# Port.net
KiCad netlist of a schematic drawn in Altium Designer
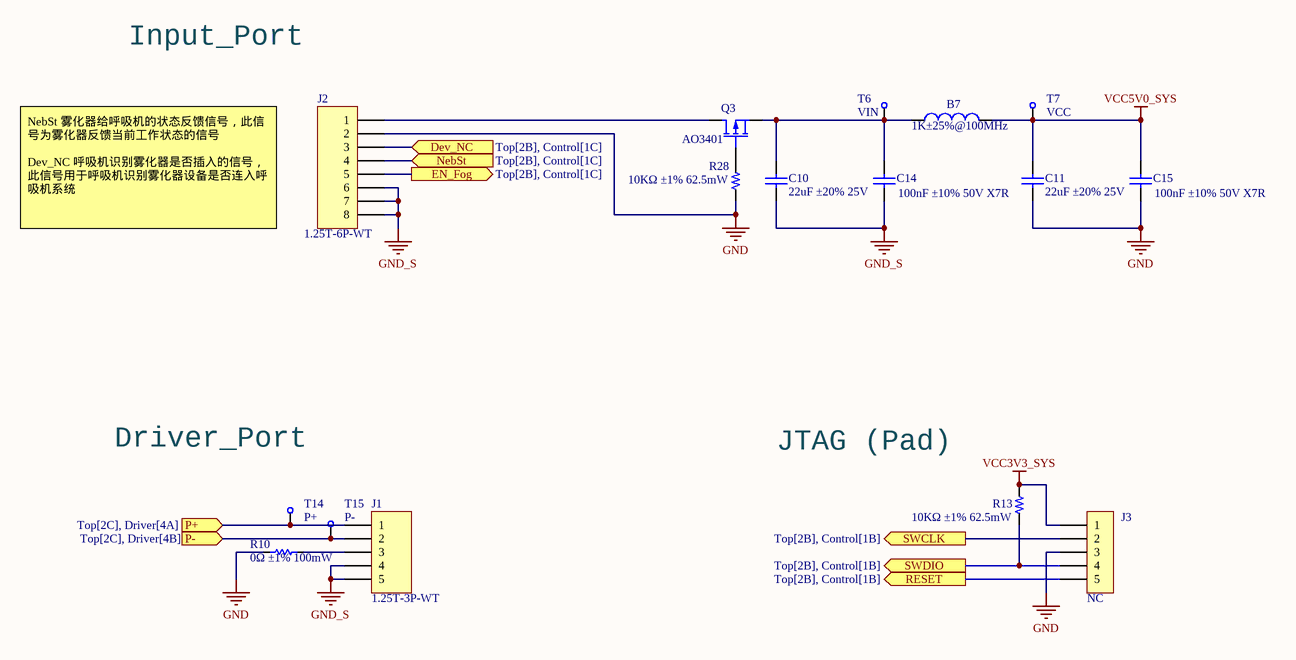
[diagram p0: Port.SchDoc]

(export (version "E")
  (design (tool "Eeschema 10.0.6"))
  (components
    (comp (ref "B7")
      (value "1K±25%@100MHz")
      (footprint "0805-B")
      (description "BLM21AG102SN1D")
      (fields (field (name "PUBLISHER") "Altium Limited"))
      (libsource (lib "Miscellaneous Devices") (part "Inductor"))
    )
    (comp (ref "C10")
      (value "22uF ±20% 25V")
      (footprint "C0805")
      (description "CL21A226MAQNNNE")
      (fields (field (name "PUBLISHER") "Altium Limited"))
      (libsource (lib "Component") (part "C0805"))
    )
    (comp (ref "C11")
      (value "22uF ±20% 25V")
      (footprint "C0805")
      (description "CL21A226MAQNNNE")
      (fields (field (name "PUBLISHER") "Altium Limited"))
      (libsource (lib "Component") (part "C0805"))
    )
    (comp (ref "C14")
      (value "100nF ±10% 50V X7R")
      (footprint "C0402")
      (description "CL05B104KO5NNNC")
      (fields (field (name "PUBLISHER") "Altium Limited"))
      (libsource (lib "Component") (part "Cap"))
    )
    (comp (ref "C15")
      (value "100nF ±10% 50V X7R")
      (footprint "C0402")
      (description "CL05B104KO5NNNC")
      (fields (field (name "PUBLISHER") "Altium Limited"))
      (libsource (lib "Component") (part "Cap"))
    )
    (comp (ref "J1")
      (value "1.25T-3P-WT")
      (footprint "WAFER_1.25MMX3P_180")
      (fields (field (name "PUBLISHER") "Altium Limited"))
      (libsource (lib "Miscellaneous Connectors") (part "Header 5"))
    )
    (comp (ref "J2")
      (value "1.25T-6P-WT")
      (footprint "WAFER_1.25MMX6P_180")
      (fields (field (name "PUBLISHER") "Altium Limited"))
      (libsource (lib "Miscellaneous Connectors") (part "Header 8"))
    )
    (comp (ref "J3")
      (value "NC")
      (footprint "JST_PH 2.00-5")
      (description "品牌：JST 型号：B5B-PH-K-S，直插，间距2.00，5pin")
      (libsource (lib "connectors") (part "JST_PH 2.00-5"))
    )
    (comp (ref "Q3")
      (value "AO3401")
      (footprint "SOT23")
      (fields (field (name "PUBLISHER") "Altium Limited"))
      (libsource (lib "Nebulizer_medical") (part "MOSFET-P"))
    )
    (comp (ref "R10")
      (value "0Ω ±1% 100mW")
      (footprint "R0603")
      (description "0603WAF0000T5E")
      (fields (field (name "PUBLISHER") "Altium Limited"))
      (libsource (lib "Component") (part "R0603"))
    )
    (comp (ref "R13")
      (value "10KΩ ±1% 62.5mW")
      (footprint "R0402")
      (description "0402WGF1002TCE")
      (libsource (lib "Device") (part "R-0603"))
    )
    (comp (ref "R28")
      (value "10KΩ ±1% 62.5mW")
      (footprint "R0402")
      (description "0402WGF1002TCE")
      (libsource (lib "Device") (part "R-0603"))
    )
    (comp (ref "T6")
      (value "VIN")
      (footprint "TP-SIP-1-Small1")
      (libsource (lib "others") (part "TP-SIP-1-Small"))
    )
    (comp (ref "T7")
      (value "VCC")
      (footprint "TP-SIP-1-Small1")
      (libsource (lib "others") (part "TP-SIP-1-Small"))
    )
    (comp (ref "T14")
      (value "P+")
      (footprint "TP-SIP-1-Small1")
      (libsource (lib "others") (part "TP-SIP-1-Small"))
    )
    (comp (ref "T15")
      (value "P-")
      (footprint "TP-SIP-1-Small1")
      (libsource (lib "others") (part "TP-SIP-1-Small"))
    )
  )
  (nets
    (net (code "1") (name "/Dev_NC") (class "Default")
      (node (ref "J2") (pin "3") (pinfunction "3_3") (pintype "passive"))
    )
    (net (code "2") (name "/EN_Fog") (class "Default")
      (node (ref "J2") (pin "5") (pinfunction "5_5") (pintype "passive"))
    )
    (net (code "3") (name "/NebSt") (class "Default")
      (node (ref "J2") (pin "4") (pinfunction "4_4") (pintype "passive"))
    )
    (net (code "4") (name "/P+") (class "Default")
      (node (ref "J1") (pin "1") (pinfunction "1_1") (pintype "passive"))
      (node (ref "T14") (pin "1") (pinfunction "1_1") (pintype "passive"))
    )
    (net (code "5") (name "/P-") (class "Default")
      (node (ref "J1") (pin "2") (pinfunction "2_2") (pintype "passive"))
      (node (ref "T15") (pin "1") (pinfunction "1_1") (pintype "passive"))
    )
    (net (code "6") (name "/RESET") (class "Default")
      (node (ref "J3") (pin "5") (pinfunction "5_5") (pintype "passive"))
    )
    (net (code "7") (name "/SWCLK") (class "Default")
      (node (ref "J3") (pin "2") (pinfunction "2_2") (pintype "passive"))
    )
    (net (code "8") (name "/SWDIO") (class "Default")
      (node (ref "J3") (pin "4") (pinfunction "4_4") (pintype "passive"))
      (node (ref "R13") (pin "1") (pinfunction "1_1") (pintype "passive"))
    )
    (net (code "9") (name "GND") (class "Default")
      (node (ref "C11") (pin "1") (pinfunction "1_1") (pintype "passive"))
      (node (ref "C15") (pin "1") (pinfunction "1_1") (pintype "passive"))
      (node (ref "J2") (pin "2") (pinfunction "2_2") (pintype "passive"))
      (node (ref "J3") (pin "3") (pinfunction "3_3") (pintype "passive"))
      (node (ref "R10") (pin "1") (pinfunction "1_1") (pintype "passive"))
      (node (ref "R28") (pin "1") (pinfunction "1_1") (pintype "passive"))
    )
    (net (code "10") (name "GND_S") (class "Default")
      (node (ref "C10") (pin "1") (pinfunction "1_1") (pintype "passive"))
      (node (ref "C14") (pin "1") (pinfunction "1_1") (pintype "passive"))
      (node (ref "J1") (pin "4") (pinfunction "4_4") (pintype "passive"))
      (node (ref "J1") (pin "5") (pinfunction "5_5") (pintype "passive"))
      (node (ref "J2") (pin "6") (pinfunction "6_6") (pintype "passive"))
      (node (ref "J2") (pin "7") (pinfunction "7_7") (pintype "passive"))
      (node (ref "J2") (pin "8") (pinfunction "8_8") (pintype "passive"))
    )
    (net (code "11") (name "Net-(J1-Pad3)") (class "Default")
      (node (ref "J1") (pin "3") (pinfunction "3_3") (pintype "passive"))
      (node (ref "R10") (pin "2") (pinfunction "2_2") (pintype "passive"))
    )
    (net (code "12") (name "Net-(Q3-D)") (class "Default")
      (node (ref "J2") (pin "1") (pinfunction "1_1") (pintype "passive"))
      (node (ref "Q3") (pin "2") (pinfunction "D_2") (pintype "passive"))
    )
    (net (code "13") (name "Net-(Q3-G)") (class "Default")
      (node (ref "Q3") (pin "1") (pinfunction "G_1") (pintype "passive"))
      (node (ref "R28") (pin "2") (pinfunction "2_2") (pintype "passive"))
    )
    (net (code "14") (name "Net-(Q3-S)") (class "Default")
      (node (ref "B7") (pin "1") (pinfunction "1_1") (pintype "passive"))
      (node (ref "C10") (pin "2") (pinfunction "2_2") (pintype "passive"))
      (node (ref "C14") (pin "2") (pinfunction "2_2") (pintype "passive"))
      (node (ref "Q3") (pin "3") (pinfunction "S_3") (pintype "passive"))
      (node (ref "T6") (pin "1") (pinfunction "1_1") (pintype "passive"))
    )
    (net (code "15") (name "VCC3V3_SYS") (class "Default")
      (node (ref "J3") (pin "1") (pinfunction "1_1") (pintype "passive"))
      (node (ref "R13") (pin "2") (pinfunction "2_2") (pintype "passive"))
    )
    (net (code "16") (name "VCC5V0_SYS") (class "Default")
      (node (ref "B7") (pin "2") (pinfunction "2_2") (pintype "passive"))
      (node (ref "C11") (pin "2") (pinfunction "2_2") (pintype "passive"))
      (node (ref "C15") (pin "2") (pinfunction "2_2") (pintype "passive"))
      (node (ref "T7") (pin "1") (pinfunction "1_1") (pintype "passive"))
    )
  )
)
